# Peripherals.net
KiCad netlist of a schematic drawn in Altium Designer
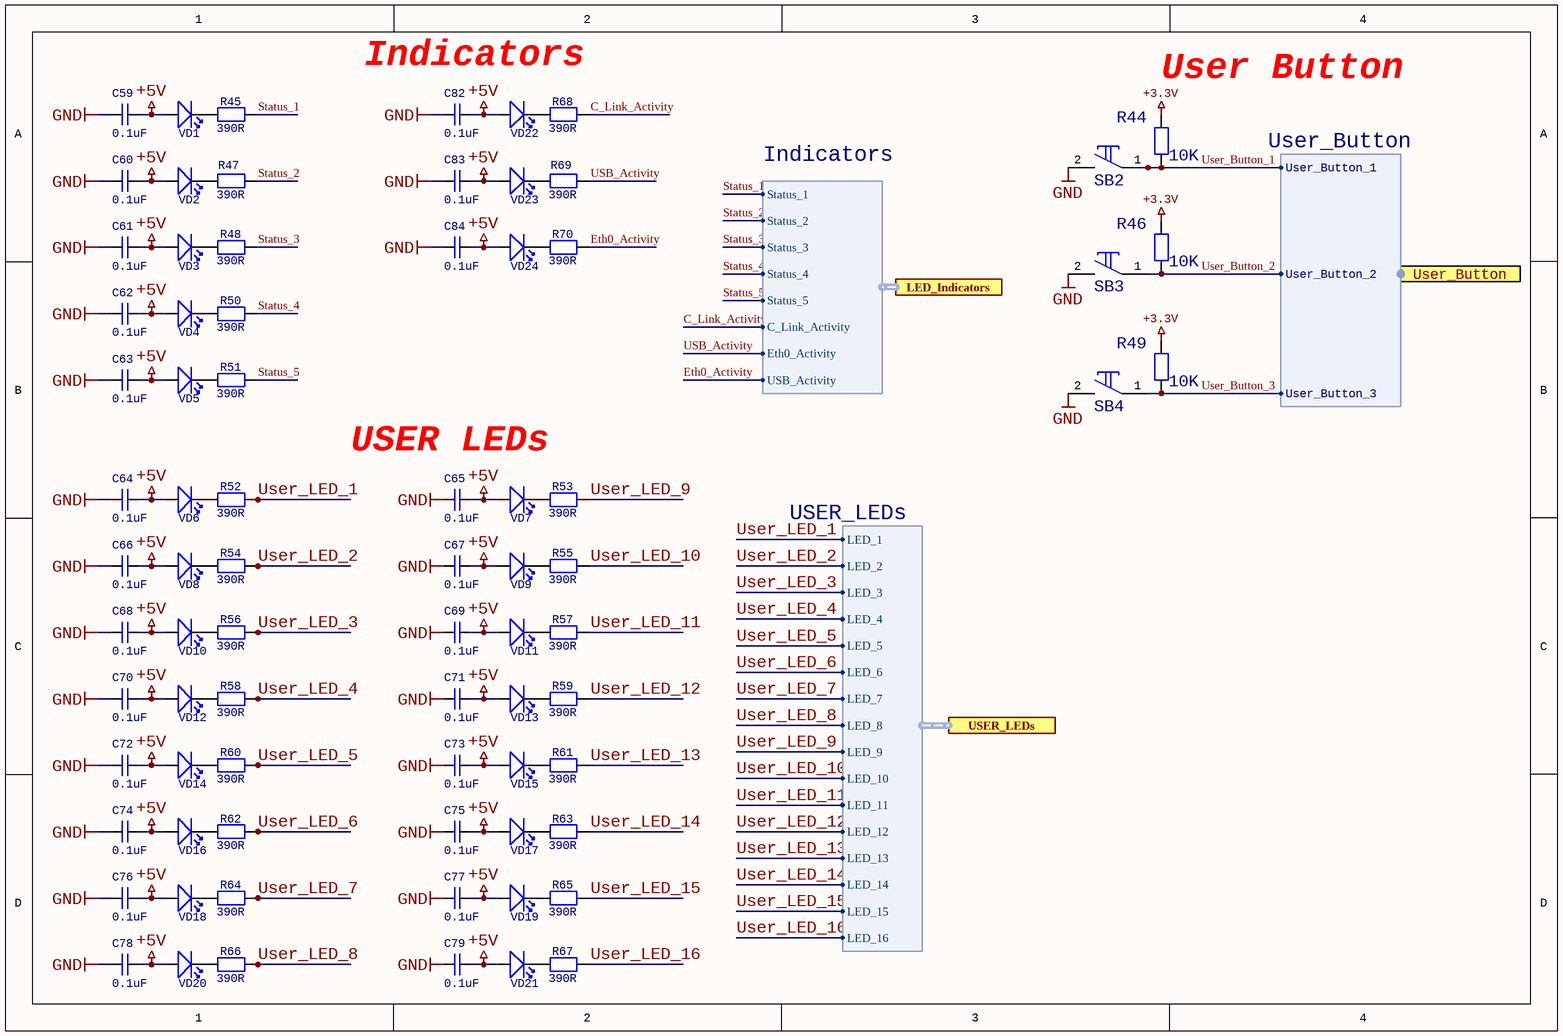
[diagram p0: Peripherals.SchDoc]

(export (version "E")
  (design (tool "Eeschema 10.0.6"))
  (components
    (comp (ref "C59")
      (value "0.1uF")
      (footprint "Passive:C_0603")
      (description "Non-polarised capacitor")
      (libsource (lib "Passive") (part "C"))
    )
    (comp (ref "C60")
      (value "0.1uF")
      (footprint "Passive:C_0603")
      (description "Non-polarised capacitor")
      (libsource (lib "Passive") (part "C"))
    )
    (comp (ref "C61")
      (value "0.1uF")
      (footprint "Passive:C_0603")
      (description "Non-polarised capacitor")
      (libsource (lib "Passive") (part "C"))
    )
    (comp (ref "C62")
      (value "0.1uF")
      (footprint "Passive:C_0603")
      (description "Non-polarised capacitor")
      (libsource (lib "Passive") (part "C"))
    )
    (comp (ref "C63")
      (value "0.1uF")
      (footprint "Passive:C_0603")
      (description "Non-polarised capacitor")
      (libsource (lib "Passive") (part "C"))
    )
    (comp (ref "C64")
      (value "0.1uF")
      (footprint "Passive:C_0603")
      (description "Non-polarised capacitor")
      (libsource (lib "Passive") (part "C"))
    )
    (comp (ref "C65")
      (value "0.1uF")
      (footprint "Passive:C_0603")
      (description "Non-polarised capacitor")
      (libsource (lib "Passive") (part "C"))
    )
    (comp (ref "C66")
      (value "0.1uF")
      (footprint "Passive:C_0603")
      (description "Non-polarised capacitor")
      (libsource (lib "Passive") (part "C"))
    )
    (comp (ref "C67")
      (value "0.1uF")
      (footprint "Passive:C_0603")
      (description "Non-polarised capacitor")
      (libsource (lib "Passive") (part "C"))
    )
    (comp (ref "C68")
      (value "0.1uF")
      (footprint "Passive:C_0603")
      (description "Non-polarised capacitor")
      (libsource (lib "Passive") (part "C"))
    )
    (comp (ref "C69")
      (value "0.1uF")
      (footprint "Passive:C_0603")
      (description "Non-polarised capacitor")
      (libsource (lib "Passive") (part "C"))
    )
    (comp (ref "C70")
      (value "0.1uF")
      (footprint "Passive:C_0603")
      (description "Non-polarised capacitor")
      (libsource (lib "Passive") (part "C"))
    )
    (comp (ref "C71")
      (value "0.1uF")
      (footprint "Passive:C_0603")
      (description "Non-polarised capacitor")
      (libsource (lib "Passive") (part "C"))
    )
    (comp (ref "C72")
      (value "0.1uF")
      (footprint "Passive:C_0603")
      (description "Non-polarised capacitor")
      (libsource (lib "Passive") (part "C"))
    )
    (comp (ref "C73")
      (value "0.1uF")
      (footprint "Passive:C_0603")
      (description "Non-polarised capacitor")
      (libsource (lib "Passive") (part "C"))
    )
    (comp (ref "C74")
      (value "0.1uF")
      (footprint "Passive:C_0603")
      (description "Non-polarised capacitor")
      (libsource (lib "Passive") (part "C"))
    )
    (comp (ref "C75")
      (value "0.1uF")
      (footprint "Passive:C_0603")
      (description "Non-polarised capacitor")
      (libsource (lib "Passive") (part "C"))
    )
    (comp (ref "C76")
      (value "0.1uF")
      (footprint "Passive:C_0603")
      (description "Non-polarised capacitor")
      (libsource (lib "Passive") (part "C"))
    )
    (comp (ref "C77")
      (value "0.1uF")
      (footprint "Passive:C_0603")
      (description "Non-polarised capacitor")
      (libsource (lib "Passive") (part "C"))
    )
    (comp (ref "C78")
      (value "0.1uF")
      (footprint "Passive:C_0603")
      (description "Non-polarised capacitor")
      (libsource (lib "Passive") (part "C"))
    )
    (comp (ref "C79")
      (value "0.1uF")
      (footprint "Passive:C_0603")
      (description "Non-polarised capacitor")
      (libsource (lib "Passive") (part "C"))
    )
    (comp (ref "C82")
      (value "0.1uF")
      (footprint "Passive:C_0603")
      (description "Non-polarised capacitor")
      (libsource (lib "Passive") (part "C"))
    )
    (comp (ref "C83")
      (value "0.1uF")
      (footprint "Passive:C_0603")
      (description "Non-polarised capacitor")
      (libsource (lib "Passive") (part "C"))
    )
    (comp (ref "C84")
      (value "0.1uF")
      (footprint "Passive:C_0603")
      (description "Non-polarised capacitor")
      (libsource (lib "Passive") (part "C"))
    )
    (comp (ref "R44") (value "10K") (footprint "Passive:R_0805") (libsource (lib "") (part "R_1")))
    (comp (ref "R45") (value "390R") (footprint "Passive:R_0603") (libsource (lib "Passive") (part "R")))
    (comp (ref "R46") (value "10K") (footprint "Passive:R_0805") (libsource (lib "") (part "R_1")))
    (comp (ref "R47") (value "390R") (footprint "Passive:R_0603") (libsource (lib "Passive") (part "R")))
    (comp (ref "R48") (value "390R") (footprint "Passive:R_0603") (libsource (lib "Passive") (part "R")))
    (comp (ref "R49") (value "10K") (footprint "Passive:R_0805") (libsource (lib "") (part "R_1")))
    (comp (ref "R50") (value "390R") (footprint "Passive:R_0603") (libsource (lib "Passive") (part "R")))
    (comp (ref "R51") (value "390R") (footprint "Passive:R_0603") (libsource (lib "Passive") (part "R")))
    (comp (ref "R52") (value "390R") (footprint "Passive:R_0603") (libsource (lib "Passive") (part "R")))
    (comp (ref "R53") (value "390R") (footprint "Passive:R_0603") (libsource (lib "Passive") (part "R")))
    (comp (ref "R54") (value "390R") (footprint "Passive:R_0603") (libsource (lib "Passive") (part "R")))
    (comp (ref "R55") (value "390R") (footprint "Passive:R_0603") (libsource (lib "Passive") (part "R")))
    (comp (ref "R56") (value "390R") (footprint "Passive:R_0603") (libsource (lib "Passive") (part "R")))
    (comp (ref "R57") (value "390R") (footprint "Passive:R_0603") (libsource (lib "Passive") (part "R")))
    (comp (ref "R58") (value "390R") (footprint "Passive:R_0603") (libsource (lib "Passive") (part "R")))
    (comp (ref "R59") (value "390R") (footprint "Passive:R_0603") (libsource (lib "Passive") (part "R")))
    (comp (ref "R60") (value "390R") (footprint "Passive:R_0603") (libsource (lib "Passive") (part "R")))
    (comp (ref "R61") (value "390R") (footprint "Passive:R_0603") (libsource (lib "Passive") (part "R")))
    (comp (ref "R62") (value "390R") (footprint "Passive:R_0603") (libsource (lib "Passive") (part "R")))
    (comp (ref "R63") (value "390R") (footprint "Passive:R_0603") (libsource (lib "Passive") (part "R")))
    (comp (ref "R64") (value "390R") (footprint "Passive:R_0603") (libsource (lib "Passive") (part "R")))
    (comp (ref "R65") (value "390R") (footprint "Passive:R_0603") (libsource (lib "Passive") (part "R")))
    (comp (ref "R66") (value "390R") (footprint "Passive:R_0603") (libsource (lib "Passive") (part "R")))
    (comp (ref "R67") (value "390R") (footprint "Passive:R_0603") (libsource (lib "Passive") (part "R")))
    (comp (ref "R68") (value "390R") (footprint "Passive:R_0603") (libsource (lib "Passive") (part "R")))
    (comp (ref "R69") (value "390R") (footprint "Passive:R_0603") (libsource (lib "Passive") (part "R")))
    (comp (ref "R70") (value "390R") (footprint "Passive:R_0603") (libsource (lib "Passive") (part "R")))
    (comp (ref "SB2")
      (value "Text")
      (footprint "Button:DTS-32")
      (fields (field (name "PUBLISHER") "Andrew Danich"))
      (libsource (lib "Passive") (part "Button"))
    )
    (comp (ref "SB3")
      (value "Text")
      (footprint "Button:DTS-32")
      (fields (field (name "PUBLISHER") "Andrew Danich"))
      (libsource (lib "Passive") (part "Button"))
    )
    (comp (ref "SB4")
      (value "Text")
      (footprint "Button:DTS-32")
      (fields (field (name "PUBLISHER") "Andrew Danich"))
      (libsource (lib "Passive") (part "Button"))
    )
    (comp (ref "VD1") (value "LED") (footprint "LD0805") (libsource (lib "Passive") (part "LED")))
    (comp (ref "VD2") (value "LED") (footprint "LD0805") (libsource (lib "Passive") (part "LED")))
    (comp (ref "VD3") (value "LED") (footprint "LD0805") (libsource (lib "Passive") (part "LED")))
    (comp (ref "VD4") (value "LED") (footprint "LD0805") (libsource (lib "Passive") (part "LED")))
    (comp (ref "VD5") (value "LED") (footprint "LD0805") (libsource (lib "Passive") (part "LED")))
    (comp (ref "VD6") (value "LED") (footprint "LD0805") (libsource (lib "Passive") (part "LED")))
    (comp (ref "VD7") (value "LED") (footprint "LD0805") (libsource (lib "Passive") (part "LED")))
    (comp (ref "VD8") (value "LED") (footprint "LD0805") (libsource (lib "Passive") (part "LED")))
    (comp (ref "VD9") (value "LED") (footprint "LD0805") (libsource (lib "Passive") (part "LED")))
    (comp (ref "VD10") (value "LED") (footprint "LD0805") (libsource (lib "Passive") (part "LED")))
    (comp (ref "VD11") (value "LED") (footprint "LD0805") (libsource (lib "Passive") (part "LED")))
    (comp (ref "VD12") (value "LED") (footprint "LD0805") (libsource (lib "Passive") (part "LED")))
    (comp (ref "VD13") (value "LED") (footprint "LD0805") (libsource (lib "Passive") (part "LED")))
    (comp (ref "VD14") (value "LED") (footprint "LD0805") (libsource (lib "Passive") (part "LED")))
    (comp (ref "VD15") (value "LED") (footprint "LD0805") (libsource (lib "Passive") (part "LED")))
    (comp (ref "VD16") (value "LED") (footprint "LD0805") (libsource (lib "Passive") (part "LED")))
    (comp (ref "VD17") (value "LED") (footprint "LD0805") (libsource (lib "Passive") (part "LED")))
    (comp (ref "VD18") (value "LED") (footprint "LD0805") (libsource (lib "Passive") (part "LED")))
    (comp (ref "VD19") (value "LED") (footprint "LD0805") (libsource (lib "Passive") (part "LED")))
    (comp (ref "VD20") (value "LED") (footprint "LD0805") (libsource (lib "Passive") (part "LED")))
    (comp (ref "VD21") (value "LED") (footprint "LD0805") (libsource (lib "Passive") (part "LED")))
    (comp (ref "VD22") (value "LED") (footprint "LD0805") (libsource (lib "Passive") (part "LED")))
    (comp (ref "VD23") (value "LED") (footprint "LD0805") (libsource (lib "Passive") (part "LED")))
    (comp (ref "VD24") (value "LED") (footprint "LD0805") (libsource (lib "Passive") (part "LED")))
  )
  (nets
    (net (code "4") (name "+3.3V") (class "Default")
      (node (ref "R44") (pin "1") (pinfunction "1_1") (pintype "passive"))
      (node (ref "R46") (pin "1") (pinfunction "1_1") (pintype "passive"))
      (node (ref "R49") (pin "1") (pinfunction "1_1") (pintype "passive"))
    )
    (net (code "5") (name "+5V") (class "Default")
      (node (ref "C59") (pin "2") (pinfunction "2_2") (pintype "passive"))
      (node (ref "C60") (pin "2") (pinfunction "2_2") (pintype "passive"))
      (node (ref "C61") (pin "2") (pinfunction "2_2") (pintype "passive"))
      (node (ref "C62") (pin "2") (pinfunction "2_2") (pintype "passive"))
      (node (ref "C63") (pin "2") (pinfunction "2_2") (pintype "passive"))
      (node (ref "C64") (pin "2") (pinfunction "2_2") (pintype "passive"))
      (node (ref "C65") (pin "2") (pinfunction "2_2") (pintype "passive"))
      (node (ref "C66") (pin "2") (pinfunction "2_2") (pintype "passive"))
      (node (ref "C67") (pin "2") (pinfunction "2_2") (pintype "passive"))
      (node (ref "C68") (pin "2") (pinfunction "2_2") (pintype "passive"))
      (node (ref "C69") (pin "2") (pinfunction "2_2") (pintype "passive"))
      (node (ref "C70") (pin "2") (pinfunction "2_2") (pintype "passive"))
      (node (ref "C71") (pin "2") (pinfunction "2_2") (pintype "passive"))
      (node (ref "C72") (pin "2") (pinfunction "2_2") (pintype "passive"))
      (node (ref "C73") (pin "2") (pinfunction "2_2") (pintype "passive"))
      (node (ref "C74") (pin "2") (pinfunction "2_2") (pintype "passive"))
      (node (ref "C75") (pin "2") (pinfunction "2_2") (pintype "passive"))
      (node (ref "C76") (pin "2") (pinfunction "2_2") (pintype "passive"))
      (node (ref "C77") (pin "2") (pinfunction "2_2") (pintype "passive"))
      (node (ref "C78") (pin "2") (pinfunction "2_2") (pintype "passive"))
      (node (ref "C79") (pin "2") (pinfunction "2_2") (pintype "passive"))
      (node (ref "C82") (pin "2") (pinfunction "2_2") (pintype "passive"))
      (node (ref "C83") (pin "2") (pinfunction "2_2") (pintype "passive"))
      (node (ref "C84") (pin "2") (pinfunction "2_2") (pintype "passive"))
      (node (ref "VD1") (pin "1") (pinfunction "+_1") (pintype "passive"))
      (node (ref "VD10") (pin "1") (pinfunction "+_1") (pintype "passive"))
      (node (ref "VD11") (pin "1") (pinfunction "+_1") (pintype "passive"))
      (node (ref "VD12") (pin "1") (pinfunction "+_1") (pintype "passive"))
      (node (ref "VD13") (pin "1") (pinfunction "+_1") (pintype "passive"))
      (node (ref "VD14") (pin "1") (pinfunction "+_1") (pintype "passive"))
      (node (ref "VD15") (pin "1") (pinfunction "+_1") (pintype "passive"))
      (node (ref "VD16") (pin "1") (pinfunction "+_1") (pintype "passive"))
      (node (ref "VD17") (pin "1") (pinfunction "+_1") (pintype "passive"))
      (node (ref "VD18") (pin "1") (pinfunction "+_1") (pintype "passive"))
      (node (ref "VD19") (pin "1") (pinfunction "+_1") (pintype "passive"))
      (node (ref "VD2") (pin "1") (pinfunction "+_1") (pintype "passive"))
      (node (ref "VD20") (pin "1") (pinfunction "+_1") (pintype "passive"))
      (node (ref "VD21") (pin "1") (pinfunction "+_1") (pintype "passive"))
      (node (ref "VD22") (pin "1") (pinfunction "+_1") (pintype "passive"))
      (node (ref "VD23") (pin "1") (pinfunction "+_1") (pintype "passive"))
      (node (ref "VD24") (pin "1") (pinfunction "+_1") (pintype "passive"))
      (node (ref "VD3") (pin "1") (pinfunction "+_1") (pintype "passive"))
      (node (ref "VD4") (pin "1") (pinfunction "+_1") (pintype "passive"))
      (node (ref "VD5") (pin "1") (pinfunction "+_1") (pintype "passive"))
      (node (ref "VD6") (pin "1") (pinfunction "+_1") (pintype "passive"))
      (node (ref "VD7") (pin "1") (pinfunction "+_1") (pintype "passive"))
      (node (ref "VD8") (pin "1") (pinfunction "+_1") (pintype "passive"))
      (node (ref "VD9") (pin "1") (pinfunction "+_1") (pintype "passive"))
    )
    (net (code "6") (name "/C_Link_Activity") (class "Default")
      (node (ref "R68") (pin "2") (pinfunction "2_2") (pintype "passive"))
    )
    (net (code "7") (name "/Eth0_Activity") (class "Default")
      (node (ref "R70") (pin "2") (pinfunction "2_2") (pintype "passive"))
    )
    (net (code "8") (name "/Status_1") (class "Default")
      (node (ref "R45") (pin "2") (pinfunction "2_2") (pintype "passive"))
    )
    (net (code "9") (name "/Status_2") (class "Default")
      (node (ref "R47") (pin "2") (pinfunction "2_2") (pintype "passive"))
    )
    (net (code "10") (name "/Status_3") (class "Default")
      (node (ref "R48") (pin "2") (pinfunction "2_2") (pintype "passive"))
    )
    (net (code "11") (name "/Status_4") (class "Default")
      (node (ref "R50") (pin "2") (pinfunction "2_2") (pintype "passive"))
    )
    (net (code "12") (name "/Status_5") (class "Default")
      (node (ref "R51") (pin "2") (pinfunction "2_2") (pintype "passive"))
    )
    (net (code "13") (name "/USB_Activity") (class "Default")
      (node (ref "R69") (pin "2") (pinfunction "2_2") (pintype "passive"))
    )
    (net (code "14") (name "/User_Button_1") (class "Default")
      (node (ref "R44") (pin "2") (pinfunction "2_2") (pintype "passive"))
      (node (ref "SB2") (pin "1") (pinfunction "1_1") (pintype "passive"))
    )
    (net (code "15") (name "/User_Button_2") (class "Default")
      (node (ref "R46") (pin "2") (pinfunction "2_2") (pintype "passive"))
      (node (ref "SB3") (pin "1") (pinfunction "1_1") (pintype "passive"))
    )
    (net (code "16") (name "/User_Button_3") (class "Default")
      (node (ref "R49") (pin "2") (pinfunction "2_2") (pintype "passive"))
      (node (ref "SB4") (pin "1") (pinfunction "1_1") (pintype "passive"))
    )
    (net (code "17") (name "/User_LED_1") (class "Default")
      (node (ref "R52") (pin "2") (pinfunction "2_2") (pintype "passive"))
    )
    (net (code "18") (name "/User_LED_2") (class "Default")
      (node (ref "R54") (pin "2") (pinfunction "2_2") (pintype "passive"))
    )
    (net (code "19") (name "/User_LED_3") (class "Default")
      (node (ref "R56") (pin "2") (pinfunction "2_2") (pintype "passive"))
    )
    (net (code "20") (name "/User_LED_4") (class "Default")
      (node (ref "R58") (pin "2") (pinfunction "2_2") (pintype "passive"))
    )
    (net (code "21") (name "/User_LED_5") (class "Default")
      (node (ref "R60") (pin "2") (pinfunction "2_2") (pintype "passive"))
    )
    (net (code "22") (name "/User_LED_6") (class "Default")
      (node (ref "R62") (pin "2") (pinfunction "2_2") (pintype "passive"))
    )
    (net (code "23") (name "/User_LED_7") (class "Default")
      (node (ref "R64") (pin "2") (pinfunction "2_2") (pintype "passive"))
    )
    (net (code "24") (name "/User_LED_8") (class "Default")
      (node (ref "R66") (pin "2") (pinfunction "2_2") (pintype "passive"))
    )
    (net (code "25") (name "/User_LED_9") (class "Default")
      (node (ref "R53") (pin "2") (pinfunction "2_2") (pintype "passive"))
    )
    (net (code "26") (name "/User_LED_10") (class "Default")
      (node (ref "R55") (pin "2") (pinfunction "2_2") (pintype "passive"))
    )
    (net (code "27") (name "/User_LED_11") (class "Default")
      (node (ref "R57") (pin "2") (pinfunction "2_2") (pintype "passive"))
    )
    (net (code "28") (name "/User_LED_12") (class "Default")
      (node (ref "R59") (pin "2") (pinfunction "2_2") (pintype "passive"))
    )
    (net (code "29") (name "/User_LED_13") (class "Default")
      (node (ref "R61") (pin "2") (pinfunction "2_2") (pintype "passive"))
    )
    (net (code "30") (name "/User_LED_14") (class "Default")
      (node (ref "R63") (pin "2") (pinfunction "2_2") (pintype "passive"))
    )
    (net (code "31") (name "/User_LED_15") (class "Default")
      (node (ref "R65") (pin "2") (pinfunction "2_2") (pintype "passive"))
    )
    (net (code "32") (name "/User_LED_16") (class "Default")
      (node (ref "R67") (pin "2") (pinfunction "2_2") (pintype "passive"))
    )
    (net (code "36") (name "GND") (class "Default")
      (node (ref "C59") (pin "1") (pinfunction "1_1") (pintype "passive"))
      (node (ref "C60") (pin "1") (pinfunction "1_1") (pintype "passive"))
      (node (ref "C61") (pin "1") (pinfunction "1_1") (pintype "passive"))
      (node (ref "C62") (pin "1") (pinfunction "1_1") (pintype "passive"))
      (node (ref "C63") (pin "1") (pinfunction "1_1") (pintype "passive"))
      (node (ref "C64") (pin "1") (pinfunction "1_1") (pintype "passive"))
      (node (ref "C65") (pin "1") (pinfunction "1_1") (pintype "passive"))
      (node (ref "C66") (pin "1") (pinfunction "1_1") (pintype "passive"))
      (node (ref "C67") (pin "1") (pinfunction "1_1") (pintype "passive"))
      (node (ref "C68") (pin "1") (pinfunction "1_1") (pintype "passive"))
      (node (ref "C69") (pin "1") (pinfunction "1_1") (pintype "passive"))
      (node (ref "C70") (pin "1") (pinfunction "1_1") (pintype "passive"))
      (node (ref "C71") (pin "1") (pinfunction "1_1") (pintype "passive"))
      (node (ref "C72") (pin "1") (pinfunction "1_1") (pintype "passive"))
      (node (ref "C73") (pin "1") (pinfunction "1_1") (pintype "passive"))
      (node (ref "C74") (pin "1") (pinfunction "1_1") (pintype "passive"))
      (node (ref "C75") (pin "1") (pinfunction "1_1") (pintype "passive"))
      (node (ref "C76") (pin "1") (pinfunction "1_1") (pintype "passive"))
      (node (ref "C77") (pin "1") (pinfunction "1_1") (pintype "passive"))
      (node (ref "C78") (pin "1") (pinfunction "1_1") (pintype "passive"))
      (node (ref "C79") (pin "1") (pinfunction "1_1") (pintype "passive"))
      (node (ref "C82") (pin "1") (pinfunction "1_1") (pintype "passive"))
      (node (ref "C83") (pin "1") (pinfunction "1_1") (pintype "passive"))
      (node (ref "C84") (pin "1") (pinfunction "1_1") (pintype "passive"))
      (node (ref "SB2") (pin "2") (pinfunction "2_2") (pintype "passive"))
      (node (ref "SB3") (pin "2") (pinfunction "2_2") (pintype "passive"))
      (node (ref "SB4") (pin "2") (pinfunction "2_2") (pintype "passive"))
    )
    (net (code "37") (name "Net-(VD1--)") (class "Default")
      (node (ref "R45") (pin "1") (pinfunction "1_1") (pintype "passive"))
      (node (ref "VD1") (pin "2") (pinfunction "-_2") (pintype "passive"))
    )
    (net (code "38") (name "Net-(VD2--)") (class "Default")
      (node (ref "R47") (pin "1") (pinfunction "1_1") (pintype "passive"))
      (node (ref "VD2") (pin "2") (pinfunction "-_2") (pintype "passive"))
    )
    (net (code "39") (name "Net-(VD3--)") (class "Default")
      (node (ref "R48") (pin "1") (pinfunction "1_1") (pintype "passive"))
      (node (ref "VD3") (pin "2") (pinfunction "-_2") (pintype "passive"))
    )
    (net (code "40") (name "Net-(VD4--)") (class "Default")
      (node (ref "R50") (pin "1") (pinfunction "1_1") (pintype "passive"))
      (node (ref "VD4") (pin "2") (pinfunction "-_2") (pintype "passive"))
    )
    (net (code "41") (name "Net-(VD5--)") (class "Default")
      (node (ref "R51") (pin "1") (pinfunction "1_1") (pintype "passive"))
      (node (ref "VD5") (pin "2") (pinfunction "-_2") (pintype "passive"))
    )
    (net (code "42") (name "Net-(VD6--)") (class "Default")
      (node (ref "R52") (pin "1") (pinfunction "1_1") (pintype "passive"))
      (node (ref "VD6") (pin "2") (pinfunction "-_2") (pintype "passive"))
    )
    (net (code "43") (name "Net-(VD7--)") (class "Default")
      (node (ref "R53") (pin "1") (pinfunction "1_1") (pintype "passive"))
      (node (ref "VD7") (pin "2") (pinfunction "-_2") (pintype "passive"))
    )
    (net (code "44") (name "Net-(VD8--)") (class "Default")
      (node (ref "R54") (pin "1") (pinfunction "1_1") (pintype "passive"))
      (node (ref "VD8") (pin "2") (pinfunction "-_2") (pintype "passive"))
    )
    (net (code "45") (name "Net-(VD9--)") (class "Default")
      (node (ref "R55") (pin "1") (pinfunction "1_1") (pintype "passive"))
      (node (ref "VD9") (pin "2") (pinfunction "-_2") (pintype "passive"))
    )
    (net (code "46") (name "Net-(VD10--)") (class "Default")
      (node (ref "R56") (pin "1") (pinfunction "1_1") (pintype "passive"))
      (node (ref "VD10") (pin "2") (pinfunction "-_2") (pintype "passive"))
    )
    (net (code "47") (name "Net-(VD11--)") (class "Default")
      (node (ref "R57") (pin "1") (pinfunction "1_1") (pintype "passive"))
      (node (ref "VD11") (pin "2") (pinfunction "-_2") (pintype "passive"))
    )
    (net (code "48") (name "Net-(VD12--)") (class "Default")
      (node (ref "R58") (pin "1") (pinfunction "1_1") (pintype "passive"))
      (node (ref "VD12") (pin "2") (pinfunction "-_2") (pintype "passive"))
    )
    (net (code "49") (name "Net-(VD13--)") (class "Default")
      (node (ref "R59") (pin "1") (pinfunction "1_1") (pintype "passive"))
      (node (ref "VD13") (pin "2") (pinfunction "-_2") (pintype "passive"))
    )
    (net (code "50") (name "Net-(VD14--)") (class "Default")
      (node (ref "R60") (pin "1") (pinfunction "1_1") (pintype "passive"))
      (node (ref "VD14") (pin "2") (pinfunction "-_2") (pintype "passive"))
    )
    (net (code "51") (name "Net-(VD15--)") (class "Default")
      (node (ref "R61") (pin "1") (pinfunction "1_1") (pintype "passive"))
      (node (ref "VD15") (pin "2") (pinfunction "-_2") (pintype "passive"))
    )
    (net (code "52") (name "Net-(VD16--)") (class "Default")
      (node (ref "R62") (pin "1") (pinfunction "1_1") (pintype "passive"))
      (node (ref "VD16") (pin "2") (pinfunction "-_2") (pintype "passive"))
    )
    (net (code "53") (name "Net-(VD17--)") (class "Default")
      (node (ref "R63") (pin "1") (pinfunction "1_1") (pintype "passive"))
      (node (ref "VD17") (pin "2") (pinfunction "-_2") (pintype "passive"))
    )
    (net (code "54") (name "Net-(VD18--)") (class "Default")
      (node (ref "R64") (pin "1") (pinfunction "1_1") (pintype "passive"))
      (node (ref "VD18") (pin "2") (pinfunction "-_2") (pintype "passive"))
    )
    (net (code "55") (name "Net-(VD19--)") (class "Default")
      (node (ref "R65") (pin "1") (pinfunction "1_1") (pintype "passive"))
      (node (ref "VD19") (pin "2") (pinfunction "-_2") (pintype "passive"))
    )
    (net (code "56") (name "Net-(VD20--)") (class "Default")
      (node (ref "R66") (pin "1") (pinfunction "1_1") (pintype "passive"))
      (node (ref "VD20") (pin "2") (pinfunction "-_2") (pintype "passive"))
    )
    (net (code "57") (name "Net-(VD21--)") (class "Default")
      (node (ref "R67") (pin "1") (pinfunction "1_1") (pintype "passive"))
      (node (ref "VD21") (pin "2") (pinfunction "-_2") (pintype "passive"))
    )
    (net (code "58") (name "Net-(VD22--)") (class "Default")
      (node (ref "R68") (pin "1") (pinfunction "1_1") (pintype "passive"))
      (node (ref "VD22") (pin "2") (pinfunction "-_2") (pintype "passive"))
    )
    (net (code "59") (name "Net-(VD23--)") (class "Default")
      (node (ref "R69") (pin "1") (pinfunction "1_1") (pintype "passive"))
      (node (ref "VD23") (pin "2") (pinfunction "-_2") (pintype "passive"))
    )
    (net (code "60") (name "Net-(VD24--)") (class "Default")
      (node (ref "R70") (pin "1") (pinfunction "1_1") (pintype "passive"))
      (node (ref "VD24") (pin "2") (pinfunction "-_2") (pintype "passive"))
    )
  )
)
